# WL-AUDIO.net
KiCad netlist of a schematic drawn in Altium Designer
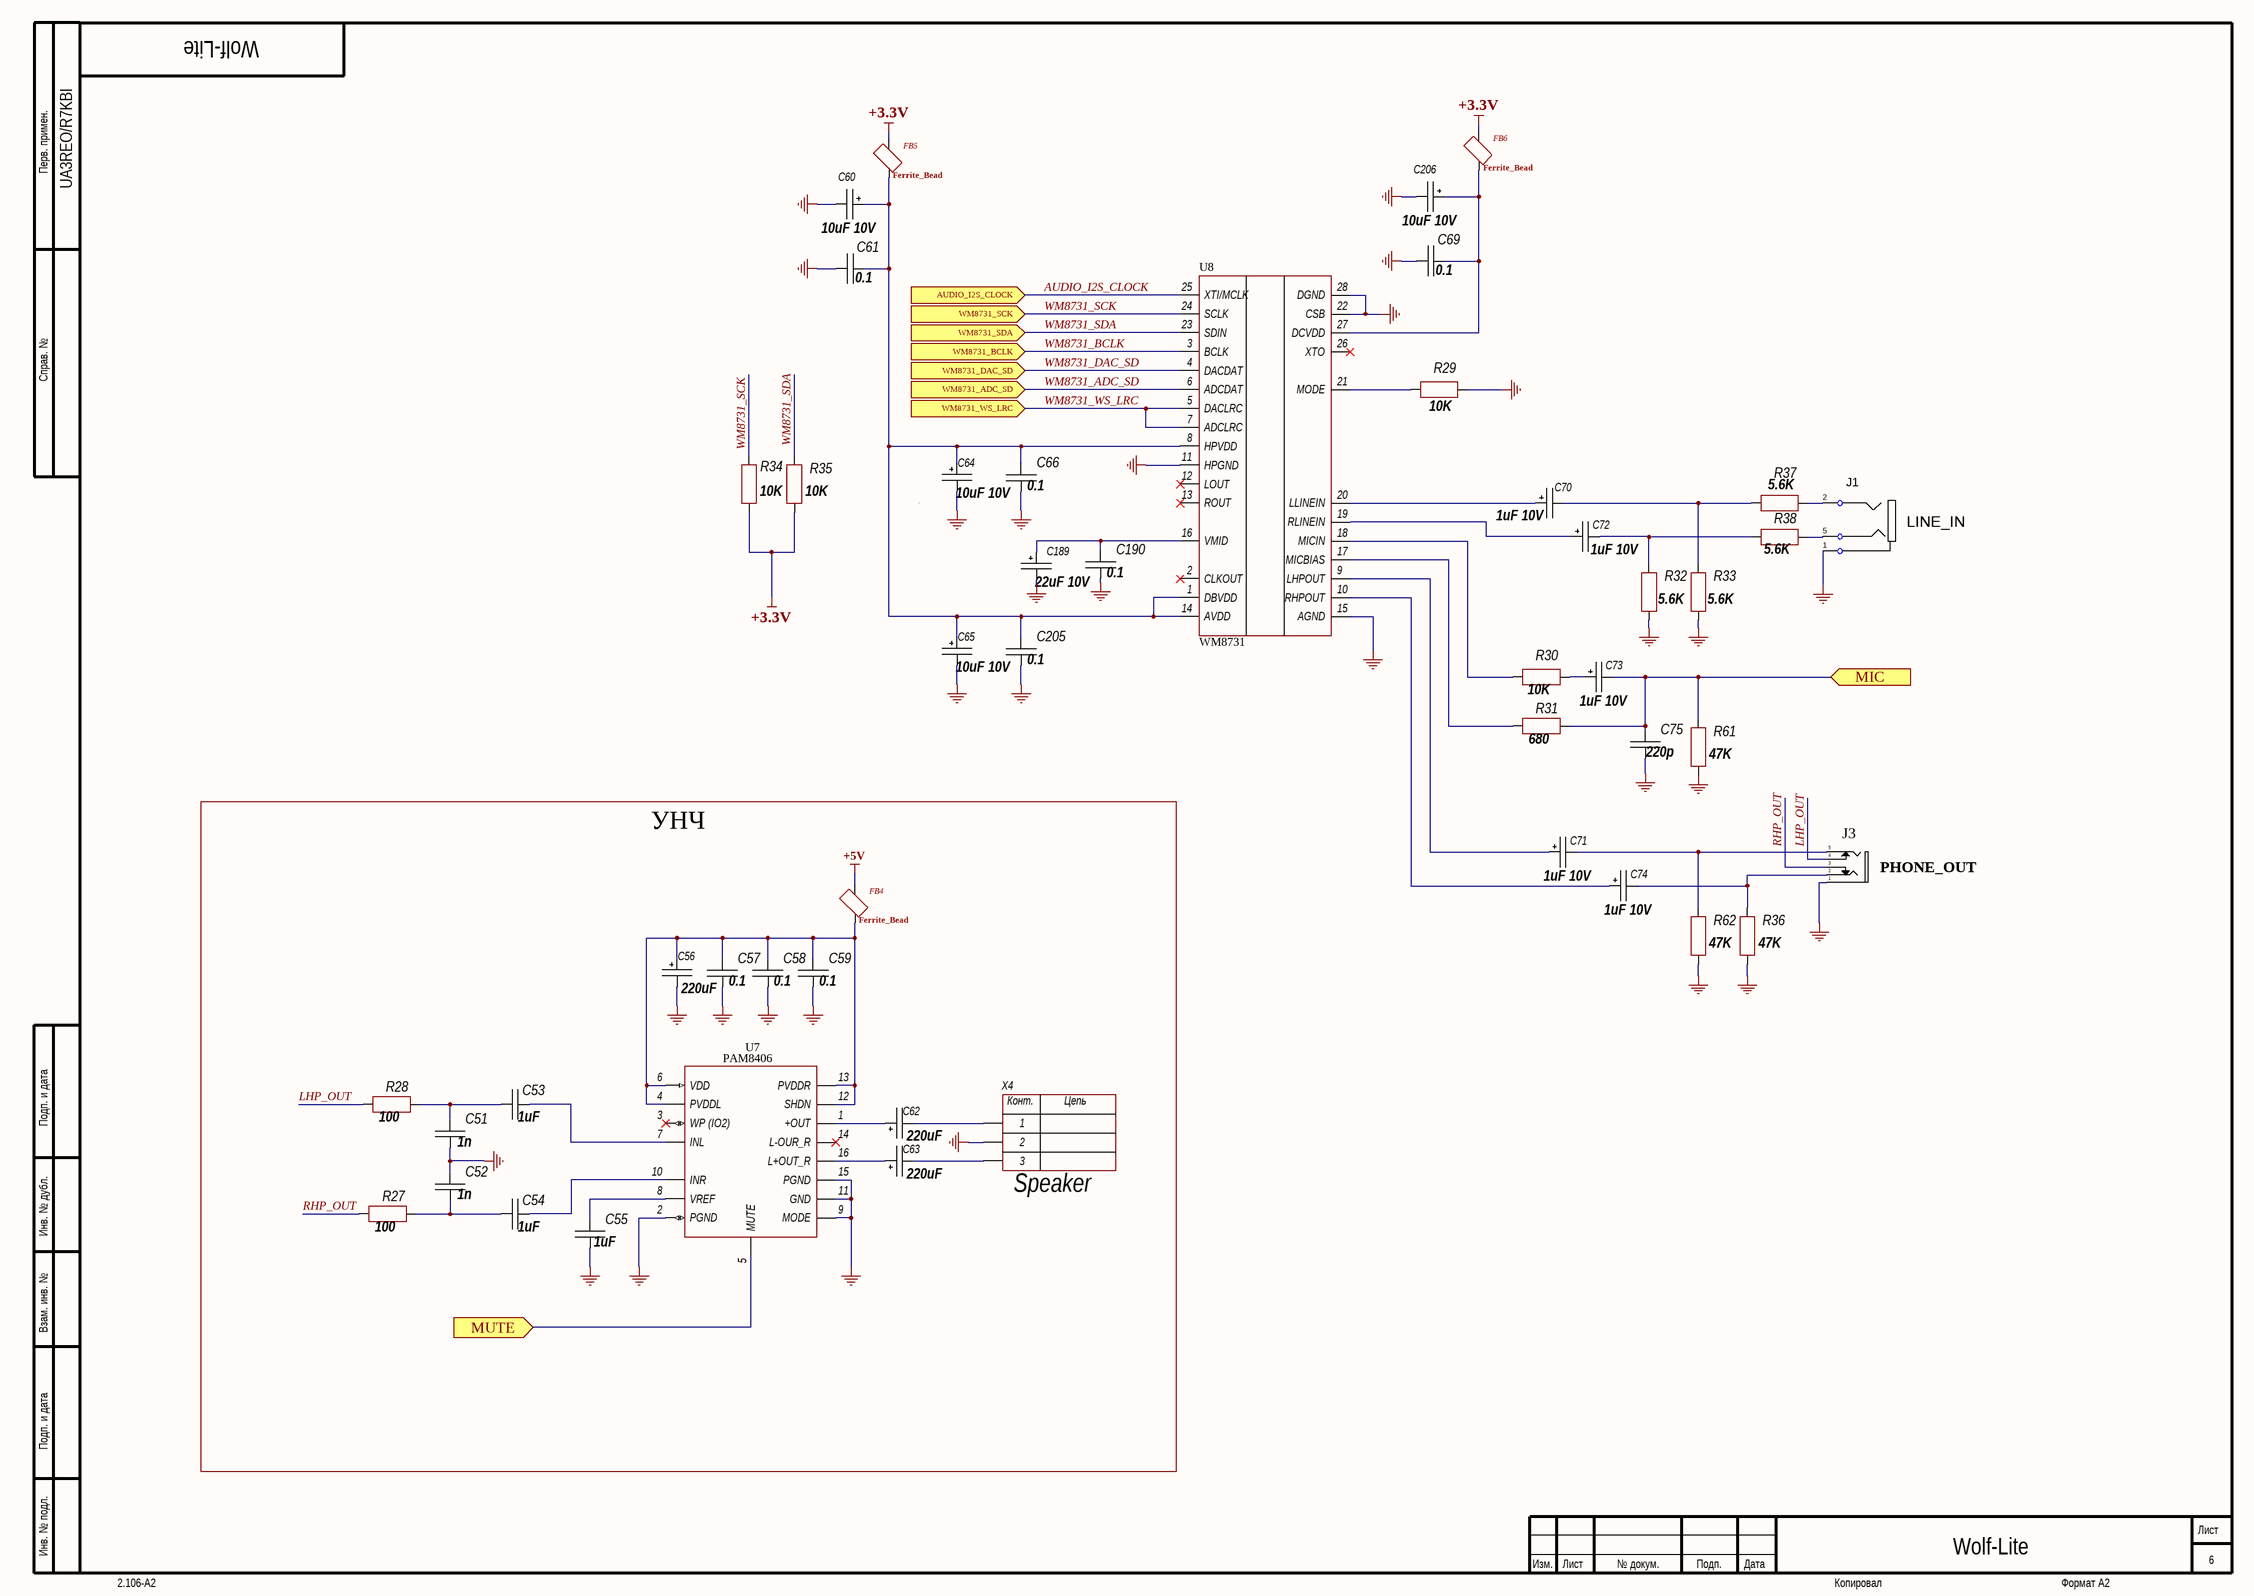
[diagram p0: WL-AUDIO.SchDoc]

(export (version "E")
  (design (tool "Eeschema 10.0.6"))
  (components
    (comp (ref "C51")
      (value "1n")
      (footprint "standard:CH0805C")
      (libsource (lib "Discrete") (part "Capacitor"))
    )
    (comp (ref "C52")
      (value "1n")
      (footprint "standard:CH0805C")
      (libsource (lib "Discrete") (part "Capacitor"))
    )
    (comp (ref "C53")
      (value "1uF")
      (footprint "standard:CH0805C")
      (libsource (lib "Discrete") (part "Capacitor"))
    )
    (comp (ref "C54")
      (value "1uF")
      (footprint "standard:CH0805C")
      (libsource (lib "Discrete") (part "Capacitor"))
    )
    (comp (ref "C55")
      (value "1uF")
      (footprint "standard:CH0805C")
      (libsource (lib "Discrete") (part "Capacitor"))
    )
    (comp (ref "C56") (value "220uF") (footprint "POLIMER-E") (libsource (lib "Discrete") (part "TantalCap")))
    (comp (ref "C57")
      (value "0.1")
      (footprint "standard:CH0805C")
      (libsource (lib "Discrete") (part "Capacitor"))
    )
    (comp (ref "C58")
      (value "0.1")
      (footprint "standard:CH0805C")
      (libsource (lib "Discrete") (part "Capacitor"))
    )
    (comp (ref "C59")
      (value "0.1")
      (footprint "standard:CH0805C")
      (libsource (lib "Discrete") (part "Capacitor"))
    )
    (comp (ref "C60")
      (value "10uF 10V")
      (footprint "standard:TANTAL_B")
      (libsource (lib "Discrete") (part "TantalCap"))
    )
    (comp (ref "C61")
      (value "0.1")
      (footprint "standard:CH0805C")
      (libsource (lib "Discrete") (part "Capacitor"))
    )
    (comp (ref "C62") (value "220uF") (footprint "POLIMER-E") (libsource (lib "Discrete") (part "TantalCap")))
    (comp (ref "C63") (value "220uF") (footprint "POLIMER-E") (libsource (lib "Discrete") (part "TantalCap")))
    (comp (ref "C64")
      (value "10uF 10V")
      (footprint "standard:TANTAL_B")
      (libsource (lib "Discrete") (part "TantalCap"))
    )
    (comp (ref "C65")
      (value "10uF 10V")
      (footprint "standard:TANTAL_B")
      (libsource (lib "Discrete") (part "TantalCap"))
    )
    (comp (ref "C66")
      (value "0.1")
      (footprint "standard:CH0805C")
      (libsource (lib "Discrete") (part "Capacitor"))
    )
    (comp (ref "C69")
      (value "0.1")
      (footprint "standard:CH0805C")
      (libsource (lib "Discrete") (part "Capacitor"))
    )
    (comp (ref "C70")
      (value "1uF 10V")
      (footprint "standard:TANTAL_A")
      (libsource (lib "Discrete") (part "TantalCap"))
    )
    (comp (ref "C71")
      (value "1uF 10V")
      (footprint "standard:TANTAL_A")
      (libsource (lib "Discrete") (part "TantalCap"))
    )
    (comp (ref "C72")
      (value "1uF 10V")
      (footprint "standard:TANTAL_A")
      (libsource (lib "Discrete") (part "TantalCap"))
    )
    (comp (ref "C73")
      (value "1uF 10V")
      (footprint "standard:TANTAL_A")
      (libsource (lib "Discrete") (part "TantalCap"))
    )
    (comp (ref "C74")
      (value "1uF 10V")
      (footprint "standard:TANTAL_A")
      (libsource (lib "Discrete") (part "TantalCap"))
    )
    (comp (ref "C75")
      (value "220p")
      (footprint "standard:CH0805C")
      (libsource (lib "Discrete") (part "Capacitor"))
    )
    (comp (ref "C189")
      (value "22uF 10V")
      (footprint "standard:TANTAL_B")
      (libsource (lib "Discrete") (part "TantalCap"))
    )
    (comp (ref "C190")
      (value "0.1")
      (footprint "standard:CH0805C")
      (libsource (lib "Discrete") (part "Capacitor"))
    )
    (comp (ref "C205")
      (value "0.1")
      (footprint "standard:CH0805C")
      (libsource (lib "Discrete") (part "Capacitor"))
    )
    (comp (ref "C206")
      (value "10uF 10V")
      (footprint "standard:TANTAL_B")
      (libsource (lib "Discrete") (part "TantalCap"))
    )
    (comp (ref "FB4") (value "Ferrite_Bead") (footprint "CH0805L") (libsource (lib "Discrete") (part "FB")))
    (comp (ref "FB5") (value "Ferrite_Bead") (footprint "CH0805L") (libsource (lib "Discrete") (part "FB")))
    (comp (ref "FB6") (value "Ferrite_Bead") (footprint "CH0805L") (libsource (lib "Discrete") (part "FB")))
    (comp (ref "J1")
      (value "LINE_IN")
      (footprint "3.5-stereo")
      (description "SJ1-3525NG")
      (libsource (lib "*") (part "SJ1-3523N"))
    )
    (comp (ref "J3") (value "PHONE_OUT") (footprint "3.5-stereo") (libsource (lib "SDR_ham") (part "PJ-3,5")))
    (comp (ref "R27")
      (value "100")
      (footprint "standard:CH0805R")
      (libsource (lib "Discrete") (part "Resistor"))
    )
    (comp (ref "R28")
      (value "100")
      (footprint "standard:CH0805R")
      (libsource (lib "Discrete") (part "Resistor"))
    )
    (comp (ref "R29")
      (value "10K")
      (footprint "standard:CH0805R")
      (libsource (lib "Discrete") (part "Resistor"))
    )
    (comp (ref "R30")
      (value "10K")
      (footprint "standard:CH0805R")
      (libsource (lib "Discrete") (part "Resistor"))
    )
    (comp (ref "R31")
      (value "680")
      (footprint "standard:CH0805R")
      (libsource (lib "Discrete") (part "Resistor"))
    )
    (comp (ref "R32") (value "5.6K") (footprint "standard:CH0805R") (libsource (lib "") (part "Resistor_1")))
    (comp (ref "R33") (value "5.6K") (footprint "standard:CH0805R") (libsource (lib "") (part "Resistor_1")))
    (comp (ref "R34") (value "10K") (footprint "standard:CH0805R") (libsource (lib "") (part "Resistor_1")))
    (comp (ref "R35") (value "10K") (footprint "standard:CH0805R") (libsource (lib "") (part "Resistor_1")))
    (comp (ref "R36") (value "47K") (footprint "standard:CH0805R") (libsource (lib "") (part "Resistor_1")))
    (comp (ref "R37")
      (value "5.6K")
      (footprint "standard:CH0805R")
      (libsource (lib "Discrete") (part "Resistor"))
    )
    (comp (ref "R38")
      (value "5.6K")
      (footprint "standard:CH0805R")
      (libsource (lib "Discrete") (part "Resistor"))
    )
    (comp (ref "R61") (value "47K") (footprint "standard:CH0805R") (libsource (lib "") (part "Resistor_1")))
    (comp (ref "R62") (value "47K") (footprint "standard:CH0805R") (libsource (lib "") (part "Resistor_1")))
    (comp (ref "U7") (value "PAM8406") (footprint "SOP-16") (libsource (lib "Digital") (part "PAM8406")))
    (comp (ref "U8") (value "WM8731") (footprint "28-SSOP") (libsource (lib "Digital") (part "WM8731")))
    (comp (ref "X4")
      (value "Speaker")
      (footprint "custom:CON: CWF-3")
      (libsource (lib "Connectors") (part "3-Connector"))
    )
  )
  (nets
    (net (code "1") (name "+3.3V") (class "Default")
      (node (ref "FB5") (pin "2") (pinfunction "2_2") (pintype "passive"))
      (node (ref "FB6") (pin "2") (pinfunction "2_2") (pintype "passive"))
      (node (ref "R34") (pin "1") (pinfunction "1_1") (pintype "passive"))
      (node (ref "R35") (pin "1") (pinfunction "1_1") (pintype "passive"))
    )
    (net (code "2") (name "+5V") (class "Default")
      (node (ref "FB4") (pin "2") (pinfunction "2_2") (pintype "passive"))
    )
    (net (code "3") (name "/AUDIO_I2S_CLOCK") (class "Default")
      (node (ref "U8") (pin "25") (pinfunction "XTI/MCLK_25") (pintype "passive"))
    )
    (net (code "4") (name "/LHP_OUT") (class "Default")
      (node (ref "J3") (pin "4") (pinfunction "5_4") (pintype "passive"))
      (node (ref "R28") (pin "1") (pinfunction "1_1") (pintype "passive"))
    )
    (net (code "5") (name "/MIC") (class "Default")
      (node (ref "C73") (pin "2") (pinfunction "2_2") (pintype "power_in"))
      (node (ref "C75") (pin "1") (pinfunction "1_1") (pintype "power_in"))
      (node (ref "R31") (pin "2") (pinfunction "2_2") (pintype "passive"))
      (node (ref "R61") (pin "2") (pinfunction "2_2") (pintype "passive"))
    )
    (net (code "6") (name "/MUTE") (class "Default")
      (node (ref "U7") (pin "5") (pinfunction "MUTE_5") (pintype "passive"))
    )
    (net (code "7") (name "/RHP_OUT") (class "Default")
      (node (ref "J3") (pin "3") (pinfunction "6_3") (pintype "passive"))
      (node (ref "R27") (pin "1") (pinfunction "1_1") (pintype "passive"))
    )
    (net (code "8") (name "/WM8731_ADC_SD") (class "Default")
      (node (ref "U8") (pin "6") (pinfunction "ADCDAT_6") (pintype "passive"))
    )
    (net (code "9") (name "/WM8731_BCLK") (class "Default")
      (node (ref "U8") (pin "3") (pinfunction "BCLK_3") (pintype "passive"))
    )
    (net (code "10") (name "/WM8731_DAC_SD") (class "Default")
      (node (ref "U8") (pin "4") (pinfunction "DACDAT_4") (pintype "passive"))
    )
    (net (code "11") (name "/WM8731_SCK") (class "Default")
      (node (ref "R34") (pin "2") (pinfunction "2_2") (pintype "passive"))
      (node (ref "U8") (pin "24") (pinfunction "SCLK_24") (pintype "passive"))
    )
    (net (code "12") (name "/WM8731_SDA") (class "Default")
      (node (ref "R35") (pin "2") (pinfunction "2_2") (pintype "passive"))
      (node (ref "U8") (pin "23") (pinfunction "SDIN_23") (pintype "passive"))
    )
    (net (code "13") (name "/WM8731_WS_LRC") (class "Default")
      (node (ref "U8") (pin "5") (pinfunction "DACLRC_5") (pintype "passive"))
      (node (ref "U8") (pin "7") (pinfunction "ADCLRC_7") (pintype "passive"))
    )
    (net (code "14") (name "GND") (class "Default")
      (node (ref "C189") (pin "2") (pinfunction "2_2") (pintype "power_in"))
      (node (ref "C190") (pin "2") (pinfunction "2_2") (pintype "power_in"))
      (node (ref "C205") (pin "2") (pinfunction "2_2") (pintype "power_in"))
      (node (ref "C206") (pin "2") (pinfunction "2_2") (pintype "power_in"))
      (node (ref "C51") (pin "2") (pinfunction "2_2") (pintype "power_in"))
      (node (ref "C52") (pin "1") (pinfunction "1_1") (pintype "power_in"))
      (node (ref "C55") (pin "2") (pinfunction "2_2") (pintype "power_in"))
      (node (ref "C56") (pin "2") (pinfunction "2_2") (pintype "power_in"))
      (node (ref "C57") (pin "2") (pinfunction "2_2") (pintype "power_in"))
      (node (ref "C58") (pin "2") (pinfunction "2_2") (pintype "power_in"))
      (node (ref "C59") (pin "2") (pinfunction "2_2") (pintype "power_in"))
      (node (ref "C60") (pin "2") (pinfunction "2_2") (pintype "power_in"))
      (node (ref "C61") (pin "2") (pinfunction "2_2") (pintype "power_in"))
      (node (ref "C64") (pin "2") (pinfunction "2_2") (pintype "power_in"))
      (node (ref "C65") (pin "2") (pinfunction "2_2") (pintype "power_in"))
      (node (ref "C66") (pin "2") (pinfunction "2_2") (pintype "power_in"))
      (node (ref "C69") (pin "2") (pinfunction "2_2") (pintype "power_in"))
      (node (ref "C75") (pin "2") (pinfunction "2_2") (pintype "power_in"))
      (node (ref "J1") (pin "1") (pinfunction "sleeve_1") (pintype "passive"))
      (node (ref "J3") (pin "1") (pinfunction "8_1") (pintype "passive"))
      (node (ref "R29") (pin "2") (pinfunction "2_2") (pintype "passive"))
      (node (ref "R32") (pin "1") (pinfunction "1_1") (pintype "passive"))
      (node (ref "R33") (pin "1") (pinfunction "1_1") (pintype "passive"))
      (node (ref "R36") (pin "1") (pinfunction "1_1") (pintype "passive"))
      (node (ref "R61") (pin "1") (pinfunction "1_1") (pintype "passive"))
      (node (ref "R62") (pin "1") (pinfunction "1_1") (pintype "passive"))
      (node (ref "U7") (pin "11") (pinfunction "GND_11") (pintype "passive"))
      (node (ref "U7") (pin "15") (pinfunction "PGND_15") (pintype "passive"))
      (node (ref "U7") (pin "2") (pinfunction "PGND_2") (pintype "bidirectional"))
      (node (ref "U7") (pin "9") (pinfunction "MODE_9") (pintype "passive"))
      (node (ref "U8") (pin "11") (pinfunction "HPGND_11") (pintype "passive"))
      (node (ref "U8") (pin "15") (pinfunction "AGND_15") (pintype "passive"))
      (node (ref "U8") (pin "22") (pinfunction "CSB_22") (pintype "passive"))
      (node (ref "U8") (pin "28") (pinfunction "DGND_28") (pintype "passive"))
      (node (ref "X4") (pin "2") (pinfunction "2_2") (pintype "passive"))
    )
    (net (code "15") (name "Net-(C51-Pad1)") (class "Default")
      (node (ref "C51") (pin "1") (pinfunction "1_1") (pintype "power_in"))
      (node (ref "C53") (pin "1") (pinfunction "1_1") (pintype "power_in"))
      (node (ref "R28") (pin "2") (pinfunction "2_2") (pintype "passive"))
    )
    (net (code "16") (name "Net-(C52-Pad2)") (class "Default")
      (node (ref "C52") (pin "2") (pinfunction "2_2") (pintype "power_in"))
      (node (ref "C54") (pin "1") (pinfunction "1_1") (pintype "power_in"))
      (node (ref "R27") (pin "2") (pinfunction "2_2") (pintype "passive"))
    )
    (net (code "17") (name "Net-(C62-Pad2)") (class "Default")
      (node (ref "C62") (pin "2") (pinfunction "2_2") (pintype "power_in"))
      (node (ref "X4") (pin "1") (pinfunction "1_1") (pintype "passive"))
    )
    (net (code "18") (name "Net-(C63-Pad2)") (class "Default")
      (node (ref "C63") (pin "2") (pinfunction "2_2") (pintype "power_in"))
      (node (ref "X4") (pin "3") (pinfunction "3_3") (pintype "power_in"))
    )
    (net (code "19") (name "Net-(C70-Pad2)") (class "Default")
      (node (ref "C70") (pin "2") (pinfunction "2_2") (pintype "power_in"))
      (node (ref "R33") (pin "2") (pinfunction "2_2") (pintype "passive"))
      (node (ref "R37") (pin "1") (pinfunction "1_1") (pintype "passive"))
    )
    (net (code "20") (name "Net-(C72-Pad2)") (class "Default")
      (node (ref "C72") (pin "2") (pinfunction "2_2") (pintype "power_in"))
      (node (ref "R32") (pin "2") (pinfunction "2_2") (pintype "passive"))
      (node (ref "R38") (pin "1") (pinfunction "1_1") (pintype "passive"))
    )
    (net (code "21") (name "Net-(C73-Pad1)") (class "Default")
      (node (ref "C73") (pin "1") (pinfunction "1_1") (pintype "power_in"))
      (node (ref "R30") (pin "2") (pinfunction "2_2") (pintype "passive"))
    )
    (net (code "22") (name "Net-(J1-ring)") (class "Default")
      (node (ref "J1") (pin "5") (pinfunction "ring_5") (pintype "passive"))
      (node (ref "R38") (pin "2") (pinfunction "2_2") (pintype "passive"))
    )
    (net (code "23") (name "Net-(J1-tip)") (class "Default")
      (node (ref "J1") (pin "2") (pinfunction "tip_2") (pintype "passive"))
      (node (ref "R37") (pin "2") (pinfunction "2_2") (pintype "passive"))
    )
    (net (code "24") (name "Net-(J3-4)") (class "Default")
      (node (ref "C71") (pin "2") (pinfunction "2_2") (pintype "power_in"))
      (node (ref "J3") (pin "5") (pinfunction "4_5") (pintype "passive"))
      (node (ref "R62") (pin "2") (pinfunction "2_2") (pintype "passive"))
    )
    (net (code "25") (name "Net-(J3-7)") (class "Default")
      (node (ref "C74") (pin "2") (pinfunction "2_2") (pintype "power_in"))
      (node (ref "J3") (pin "2") (pinfunction "7_2") (pintype "passive"))
      (node (ref "R36") (pin "2") (pinfunction "2_2") (pintype "passive"))
    )
    (net (code "26") (name "Net-(U7-+OUT)") (class "Default")
      (node (ref "C62") (pin "1") (pinfunction "1_1") (pintype "power_in"))
      (node (ref "U7") (pin "1") (pinfunction "+OUT_1") (pintype "passive"))
    )
    (net (code "27") (name "Net-(U7-INL)") (class "Default")
      (node (ref "C53") (pin "2") (pinfunction "2_2") (pintype "power_in"))
      (node (ref "U7") (pin "7") (pinfunction "INL_7") (pintype "passive"))
    )
    (net (code "28") (name "Net-(U7-INR)") (class "Default")
      (node (ref "C54") (pin "2") (pinfunction "2_2") (pintype "power_in"))
      (node (ref "U7") (pin "10") (pinfunction "INR_10") (pintype "passive"))
    )
    (net (code "29") (name "Net-(U7-L+OUT_R)") (class "Default")
      (node (ref "C63") (pin "1") (pinfunction "1_1") (pintype "power_in"))
      (node (ref "U7") (pin "16") (pinfunction "L+OUT_R_16") (pintype "passive"))
    )
    (net (code "30") (name "Net-(U7-PVDDL)") (class "Default")
      (node (ref "C56") (pin "1") (pinfunction "1_1") (pintype "power_in"))
      (node (ref "C57") (pin "1") (pinfunction "1_1") (pintype "power_in"))
      (node (ref "C58") (pin "1") (pinfunction "1_1") (pintype "power_in"))
      (node (ref "C59") (pin "1") (pinfunction "1_1") (pintype "power_in"))
      (node (ref "FB4") (pin "1") (pinfunction "1_1") (pintype "passive"))
      (node (ref "U7") (pin "12") (pinfunction "SHDN_12") (pintype "passive"))
      (node (ref "U7") (pin "13") (pinfunction "PVDDR_13") (pintype "passive"))
      (node (ref "U7") (pin "4") (pinfunction "PVDDL_4") (pintype "power_in"))
      (node (ref "U7") (pin "6") (pinfunction "VDD_6") (pintype "input"))
    )
    (net (code "31") (name "Net-(U7-VREF)") (class "Default")
      (node (ref "C55") (pin "1") (pinfunction "1_1") (pintype "power_in"))
      (node (ref "U7") (pin "8") (pinfunction "VREF_8") (pintype "power_in"))
    )
    (net (code "32") (name "Net-(U8-AVDD)") (class "Default")
      (node (ref "C205") (pin "1") (pinfunction "1_1") (pintype "power_in"))
      (node (ref "C60") (pin "1") (pinfunction "1_1") (pintype "power_in"))
      (node (ref "C61") (pin "1") (pinfunction "1_1") (pintype "power_in"))
      (node (ref "C64") (pin "1") (pinfunction "1_1") (pintype "power_in"))
      (node (ref "C65") (pin "1") (pinfunction "1_1") (pintype "power_in"))
      (node (ref "C66") (pin "1") (pinfunction "1_1") (pintype "power_in"))
      (node (ref "FB5") (pin "1") (pinfunction "1_1") (pintype "passive"))
      (node (ref "U8") (pin "1") (pinfunction "DBVDD_1") (pintype "passive"))
      (node (ref "U8") (pin "14") (pinfunction "AVDD_14") (pintype "passive"))
      (node (ref "U8") (pin "8") (pinfunction "HPVDD_8") (pintype "passive"))
    )
    (net (code "33") (name "Net-(U8-DCVDD)") (class "Default")
      (node (ref "C206") (pin "1") (pinfunction "1_1") (pintype "power_in"))
      (node (ref "C69") (pin "1") (pinfunction "1_1") (pintype "power_in"))
      (node (ref "FB6") (pin "1") (pinfunction "1_1") (pintype "passive"))
      (node (ref "U8") (pin "27") (pinfunction "DCVDD_27") (pintype "passive"))
    )
    (net (code "34") (name "Net-(U8-LHPOUT)") (class "Default")
      (node (ref "C71") (pin "1") (pinfunction "1_1") (pintype "power_in"))
      (node (ref "U8") (pin "9") (pinfunction "LHPOUT_9") (pintype "passive"))
    )
    (net (code "35") (name "Net-(U8-LLINEIN)") (class "Default")
      (node (ref "C70") (pin "1") (pinfunction "1_1") (pintype "power_in"))
      (node (ref "U8") (pin "20") (pinfunction "LLINEIN_20") (pintype "passive"))
    )
    (net (code "36") (name "Net-(U8-MICBIAS)") (class "Default")
      (node (ref "R31") (pin "1") (pinfunction "1_1") (pintype "passive"))
      (node (ref "U8") (pin "17") (pinfunction "MICBIAS_17") (pintype "passive"))
    )
    (net (code "37") (name "Net-(U8-MICIN)") (class "Default")
      (node (ref "R30") (pin "1") (pinfunction "1_1") (pintype "passive"))
      (node (ref "U8") (pin "18") (pinfunction "MICIN_18") (pintype "passive"))
    )
    (net (code "38") (name "Net-(U8-MODE)") (class "Default")
      (node (ref "R29") (pin "1") (pinfunction "1_1") (pintype "passive"))
      (node (ref "U8") (pin "21") (pinfunction "MODE_21") (pintype "passive"))
    )
    (net (code "39") (name "Net-(U8-RHPOUT)") (class "Default")
      (node (ref "C74") (pin "1") (pinfunction "1_1") (pintype "power_in"))
      (node (ref "U8") (pin "10") (pinfunction "RHPOUT_10") (pintype "passive"))
    )
    (net (code "40") (name "Net-(U8-RLINEIN)") (class "Default")
      (node (ref "C72") (pin "1") (pinfunction "1_1") (pintype "power_in"))
      (node (ref "U8") (pin "19") (pinfunction "RLINEIN_19") (pintype "passive"))
    )
    (net (code "41") (name "Net-(U8-VMID)") (class "Default")
      (node (ref "C189") (pin "1") (pinfunction "1_1") (pintype "power_in"))
      (node (ref "C190") (pin "1") (pinfunction "1_1") (pintype "power_in"))
      (node (ref "U8") (pin "16") (pinfunction "VMID_16") (pintype "passive"))
    )
    (net (code "42") (name "unconnected-(U7-L-OUR_R-Pad14)") (class "Default")
      (node (ref "U7") (pin "14") (pinfunction "L-OUR_R_14") (pintype "passive+no_connect"))
    )
    (net (code "43") (name "unconnected-(U7-WP_(IO2)-Pad3)") (class "Default")
      (node (ref "U7") (pin "3") (pinfunction "WP_(IO2)_3") (pintype "bidirectional+no_connect"))
    )
    (net (code "44") (name "unconnected-(U8-CLKOUT-Pad2)") (class "Default")
      (node (ref "U8") (pin "2") (pinfunction "CLKOUT_2") (pintype "passive+no_connect"))
    )
    (net (code "45") (name "unconnected-(U8-LOUT-Pad12)") (class "Default")
      (node (ref "U8") (pin "12") (pinfunction "LOUT_12") (pintype "passive+no_connect"))
    )
    (net (code "46") (name "unconnected-(U8-ROUT-Pad13)") (class "Default")
      (node (ref "U8") (pin "13") (pinfunction "ROUT_13") (pintype "passive+no_connect"))
    )
    (net (code "47") (name "unconnected-(U8-XTO-Pad26)") (class "Default")
      (node (ref "U8") (pin "26") (pinfunction "XTO_26") (pintype "passive+no_connect"))
    )
  )
)
